# SPI_Diff_Slave.net
KiCad netlist of a schematic drawn in Altium Designer
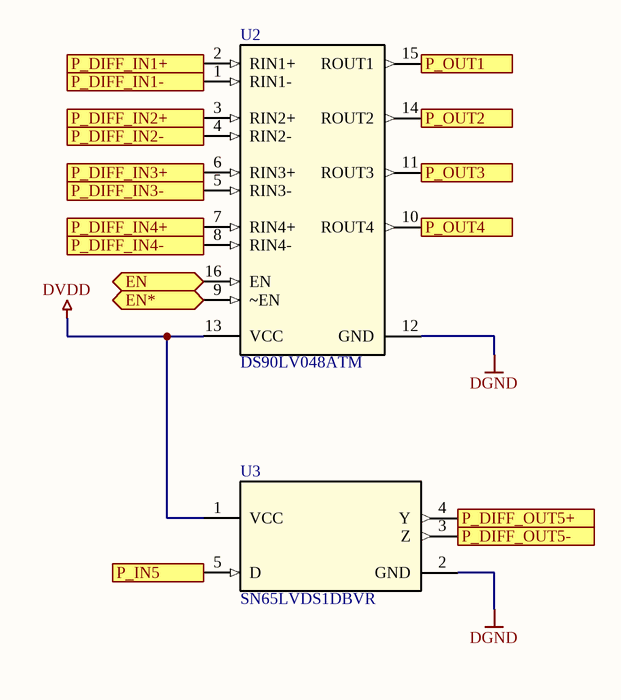
[diagram p0: SPI_Diff_Slave.SchDoc]

(export (version "E")
  (design (tool "Eeschema 10.0.6"))
  (components
    (comp (ref "U2")
      (value "DS90LV048ATM")
      (footprint "SOIC-16N")
      (description "400-Mbps LVDS quad high-speed differential receiver 16-SOIC -40 to 85")
      (fields
        (field (name "MANUFACTURER") "NationalSemiconductor")
        (field (name "COPYRIGHT") "Copyright (C) 2026 Ultra Librarian. All rights reserved.")
        (field (name "PUBLISHER") "AltiumLimited")
      )
      (libsource (lib "MyOwnParts") (part "DS90LV048ATM"))
    )
    (comp (ref "U3")
      (value "SN65LVDS1DBVR")
      (footprint "DBV5")
      (description "630-Mbps single LVDS driver 5-SOT-23 -40 to 85")
      (fields
        (field (name "ALTERNATE_PARTNUMBER") "SN65LVDS1DBVT")
        (field (name "MANUFACTURER") "Texas Instruments")
        (field (name "COPYRIGHT") "Copyright (C) 2026 Ultra Librarian. All rights reserved.")
      )
      (libsource (lib "MyOwnParts") (part "SN65LVDS1DBVR"))
    )
  )
  (nets
    (net (code "1") (name "/EN") (class "Default")
      (node (ref "U2") (pin "16") (pinfunction "EN_16") (pintype "input"))
    )
    (net (code "2") (name "/EN*") (class "Default")
      (node (ref "U2") (pin "9") (pinfunction "~EN_9") (pintype "input"))
    )
    (net (code "3") (name "/P_DIFF_IN1+") (class "Default")
      (node (ref "U2") (pin "2") (pinfunction "RIN1+_2") (pintype "input"))
    )
    (net (code "4") (name "/P_DIFF_IN1-") (class "Default")
      (node (ref "U2") (pin "1") (pinfunction "RIN1-_1") (pintype "input"))
    )
    (net (code "5") (name "/P_DIFF_IN2+") (class "Default")
      (node (ref "U2") (pin "3") (pinfunction "RIN2+_3") (pintype "input"))
    )
    (net (code "6") (name "/P_DIFF_IN2-") (class "Default")
      (node (ref "U2") (pin "4") (pinfunction "RIN2-_4") (pintype "input"))
    )
    (net (code "7") (name "/P_DIFF_IN3+") (class "Default")
      (node (ref "U2") (pin "6") (pinfunction "RIN3+_6") (pintype "input"))
    )
    (net (code "8") (name "/P_DIFF_IN3-") (class "Default")
      (node (ref "U2") (pin "5") (pinfunction "RIN3-_5") (pintype "input"))
    )
    (net (code "9") (name "/P_DIFF_IN4+") (class "Default")
      (node (ref "U2") (pin "7") (pinfunction "RIN4+_7") (pintype "input"))
    )
    (net (code "10") (name "/P_DIFF_IN4-") (class "Default")
      (node (ref "U2") (pin "8") (pinfunction "RIN4-_8") (pintype "input"))
    )
    (net (code "11") (name "/P_DIFF_OUT5+") (class "Default")
      (node (ref "U3") (pin "4") (pinfunction "Y_4") (pintype "output"))
    )
    (net (code "12") (name "/P_DIFF_OUT5-") (class "Default")
      (node (ref "U3") (pin "3") (pinfunction "Z_3") (pintype "output"))
    )
    (net (code "13") (name "/P_IN5") (class "Default")
      (node (ref "U3") (pin "5") (pinfunction "D_5") (pintype "input"))
    )
    (net (code "14") (name "/P_OUT1") (class "Default")
      (node (ref "U2") (pin "15") (pinfunction "ROUT1_15") (pintype "output"))
    )
    (net (code "15") (name "/P_OUT2") (class "Default")
      (node (ref "U2") (pin "14") (pinfunction "ROUT2_14") (pintype "output"))
    )
    (net (code "16") (name "/P_OUT3") (class "Default")
      (node (ref "U2") (pin "11") (pinfunction "ROUT3_11") (pintype "output"))
    )
    (net (code "17") (name "/P_OUT4") (class "Default")
      (node (ref "U2") (pin "10") (pinfunction "ROUT4_10") (pintype "output"))
    )
    (net (code "18") (name "DGND") (class "Default")
      (node (ref "U2") (pin "12") (pinfunction "GND_12") (pintype "power_in"))
      (node (ref "U3") (pin "2") (pinfunction "GND_2") (pintype "power_in"))
    )
    (net (code "19") (name "DVDD") (class "Default")
      (node (ref "U2") (pin "13") (pinfunction "VCC_13") (pintype "power_in"))
      (node (ref "U3") (pin "1") (pinfunction "VCC_1") (pintype "passive"))
    )
  )
)
